# RS485_CAN.net
KiCad netlist of a schematic drawn in Altium Designer
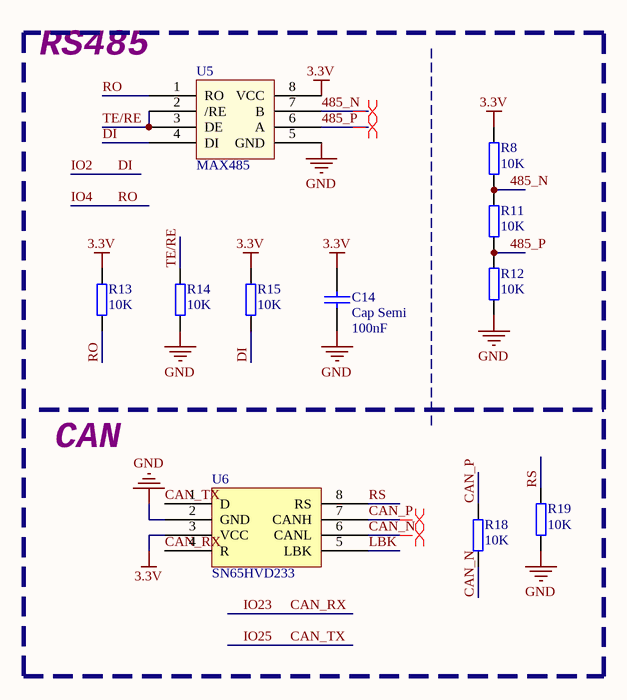
[diagram p0: RS485_CAN.SchDoc]

(export (version "E")
  (design (tool "Eeschema 10.0.6"))
  (components
    (comp (ref "C14")
      (value "Cap Semi")
      (footprint "SMT0603")
      (description "CAP SM 0603 X7R 100nF 10%")
      (fields (field (name "TOLERANCE") "±10%") (field (name "ALTIUM_VALUE") "100nF"))
      (libsource (lib "electronpowered") (part "CAP-SM-0603-X7R-100nF"))
    )
    (comp (ref "R8")
      (value "10K")
      (footprint "SMT0603")
      (description "RES SM 0603 10K")
      (fields (field (name "Comment") "Resistor"))
      (libsource (lib "electronpowered") (part "RES-SM-0603-10K"))
    )
    (comp (ref "R11")
      (value "10K")
      (footprint "SMT0603")
      (description "RES SM 0603 10K")
      (fields (field (name "Comment") "Resistor"))
      (libsource (lib "electronpowered") (part "RES-SM-0603-10K"))
    )
    (comp (ref "R12")
      (value "10K")
      (footprint "SMT0603")
      (description "RES SM 0603 10K")
      (fields (field (name "Comment") "Resistor"))
      (libsource (lib "electronpowered") (part "RES-SM-0603-10K"))
    )
    (comp (ref "R13")
      (value "10K")
      (footprint "SMT0603")
      (description "RES SM 0603 10K")
      (fields (field (name "Comment") "Resistor"))
      (libsource (lib "electronpowered") (part "RES-SM-0603-10K"))
    )
    (comp (ref "R14")
      (value "10K")
      (footprint "SMT0603")
      (description "RES SM 0603 10K")
      (fields (field (name "Comment") "Resistor"))
      (libsource (lib "electronpowered") (part "RES-SM-0603-10K"))
    )
    (comp (ref "R15")
      (value "10K")
      (footprint "SMT0603")
      (description "RES SM 0603 10K")
      (fields (field (name "Comment") "Resistor"))
      (libsource (lib "electronpowered") (part "RES-SM-0603-10K"))
    )
    (comp (ref "R18")
      (value "10K")
      (footprint "SMT0603")
      (description "RES SM 0603 10K")
      (fields (field (name "Comment") "Resistor"))
      (libsource (lib "electronpowered") (part "RES-SM-0603-10K"))
    )
    (comp (ref "R19")
      (value "10K")
      (footprint "SMT0603")
      (description "RES SM 0603 10K")
      (fields (field (name "Comment") "Resistor"))
      (libsource (lib "electronpowered") (part "RES-SM-0603-10K"))
    )
    (comp (ref "U5") (value "MAX485") (footprint "SOP8") (libsource (lib "RASHBERRY_EXTERN") (part "MAX485")))
    (comp (ref "U6")
      (value "SN65HVD233")
      (footprint "PCBComponent_1")
      (libsource (lib "SN65HVD233") (part "SN65HVD233"))
    )
  )
  (nets
    (net (code "1") (name "/485_N") (class "Default")
      (node (ref "R11") (pin "2") (pinfunction "2_2") (pintype "passive"))
      (node (ref "R8") (pin "1") (pinfunction "1_1") (pintype "passive"))
      (node (ref "U5") (pin "7") (pinfunction "B_7") (pintype "passive"))
    )
    (net (code "2") (name "/485_P") (class "Default")
      (node (ref "R11") (pin "1") (pinfunction "1_1") (pintype "passive"))
      (node (ref "R12") (pin "2") (pinfunction "2_2") (pintype "passive"))
      (node (ref "U5") (pin "6") (pinfunction "A_6") (pintype "passive"))
    )
    (net (code "3") (name "/CAN_N") (class "Default")
      (node (ref "R18") (pin "1") (pinfunction "1_1") (pintype "passive"))
      (node (ref "U6") (pin "6") (pinfunction "CANL_6") (pintype "passive"))
    )
    (net (code "4") (name "/CAN_P") (class "Default")
      (node (ref "R18") (pin "2") (pinfunction "2_2") (pintype "passive"))
      (node (ref "U6") (pin "7") (pinfunction "CANH_7") (pintype "passive"))
    )
    (net (code "5") (name "/CAN_RX") (class "Default")
      (node (ref "U6") (pin "4") (pinfunction "R_4") (pintype "passive"))
    )
    (net (code "6") (name "/CAN_TX") (class "Default")
      (node (ref "U6") (pin "1") (pinfunction "D_1") (pintype "passive"))
    )
    (net (code "7") (name "/DI") (class "Default")
      (node (ref "R15") (pin "1") (pinfunction "1_1") (pintype "passive"))
      (node (ref "U5") (pin "4") (pinfunction "DI_4") (pintype "passive"))
    )
    (net (code "8") (name "/IO4") (class "Default")
      (node (ref "R13") (pin "1") (pinfunction "1_1") (pintype "passive"))
      (node (ref "U5") (pin "1") (pinfunction "RO_1") (pintype "passive"))
    )
    (net (code "9") (name "/LBK") (class "Default")
      (node (ref "U6") (pin "5") (pinfunction "LBK_5") (pintype "passive"))
    )
    (net (code "10") (name "/RS") (class "Default")
      (node (ref "R19") (pin "2") (pinfunction "2_2") (pintype "passive"))
      (node (ref "U6") (pin "8") (pinfunction "RS_8") (pintype "passive"))
    )
    (net (code "11") (name "/TE{slash}RE") (class "Default")
      (node (ref "R14") (pin "2") (pinfunction "2_2") (pintype "passive"))
      (node (ref "U5") (pin "2") (pinfunction "/RE_2") (pintype "passive"))
      (node (ref "U5") (pin "3") (pinfunction "DE_3") (pintype "passive"))
    )
    (net (code "12") (name "3.3V") (class "Default")
      (node (ref "C14") (pin "2") (pinfunction "2_2") (pintype "passive"))
      (node (ref "R13") (pin "2") (pinfunction "2_2") (pintype "passive"))
      (node (ref "R15") (pin "2") (pinfunction "2_2") (pintype "passive"))
      (node (ref "R8") (pin "2") (pinfunction "2_2") (pintype "passive"))
      (node (ref "U5") (pin "8") (pinfunction "VCC_8") (pintype "passive"))
      (node (ref "U6") (pin "3") (pinfunction "VCC_3") (pintype "passive"))
    )
    (net (code "13") (name "GND") (class "Default")
      (node (ref "C14") (pin "1") (pinfunction "1_1") (pintype "passive"))
      (node (ref "R12") (pin "1") (pinfunction "1_1") (pintype "passive"))
      (node (ref "R14") (pin "1") (pinfunction "1_1") (pintype "passive"))
      (node (ref "R19") (pin "1") (pinfunction "1_1") (pintype "passive"))
      (node (ref "U5") (pin "5") (pinfunction "GND_5") (pintype "passive"))
      (node (ref "U6") (pin "2") (pinfunction "GND_2") (pintype "passive"))
    )
  )
)
